# Power.net
KiCad netlist of a schematic drawn in Altium Designer
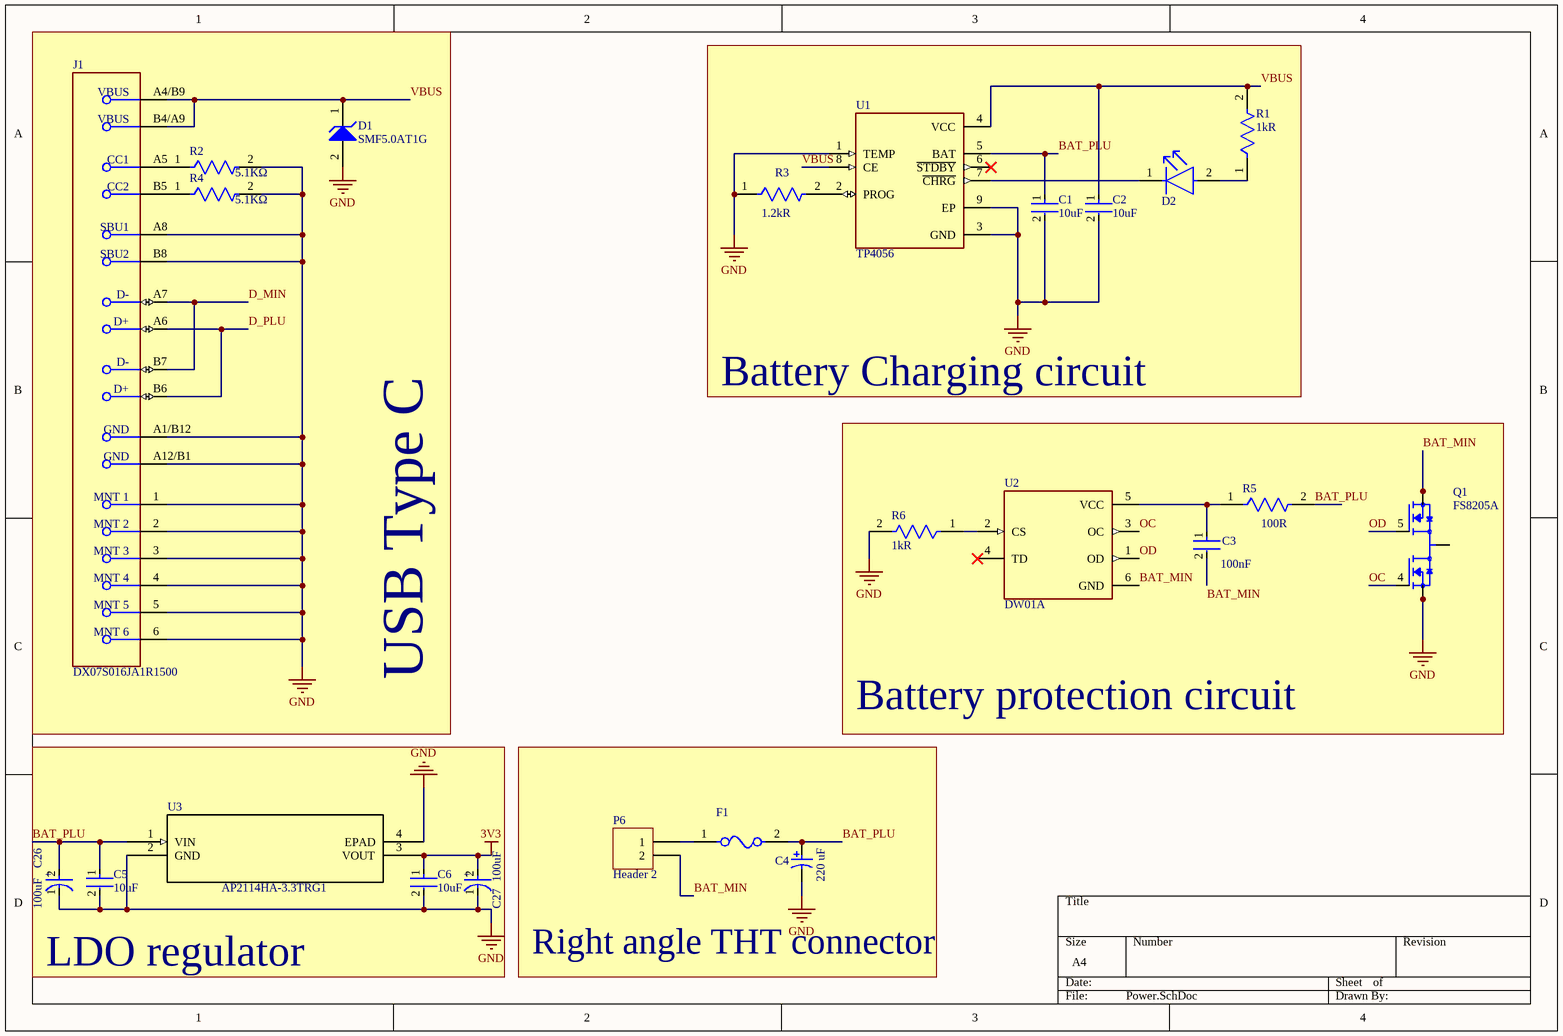
[diagram p0: Power.SchDoc]

(export (version "E")
  (design (tool "Eeschema 10.0.6"))
  (components
    (comp (ref "C1")
      (value "C0805C106J8RACAUTO")
      (footprint "FP-C0805C106J8RACAUTO-IPC_B")
      (description "CAP CER 10UF 10V X7R 0805")
      (fields
        (field (name "CAPACITANCE") "10uF")
        (field (name "TOLERANCE") "5%")
        (field (name "LCSC PART") "C15850")
      )
      (libsource (lib "Altium Content Vault") (part "02cd4be3c70576c341d710602a673aa"))
    )
    (comp (ref "C2")
      (value "C0805C106J8RACAUTO")
      (footprint "FP-C0805C106J8RACAUTO-MFG")
      (description "CAP CER 10UF 10V X7R 0805")
      (fields
        (field (name "CAPACITANCE") "10uF")
        (field (name "TOLERANCE") "5%")
        (field (name "LCSC PART") "C15850")
      )
      (libsource (lib "Altium Content Vault") (part "02cd4be3c70576c341d710602a673aa"))
    )
    (comp (ref "C3")
      (value "CC0805KKX7RYBB104")
      (footprint "FP-CC0805-EB-IPC_B")
      (description "CC0805KKX7RYBB104 Capacitor Ceramic 0.01uF 250V X7R 10% 0805 T/R")
      (fields
        (field (name "TOLERANCE") "10%")
        (field (name "CAPACITANCE") "100nF")
        (field (name "LCSC PART") "C28233")
      )
      (libsource (lib "Altium Content Vault") (part "b4654b650e69147ec39a6b967a45e02"))
    )
    (comp (ref "C4")
      (value "UUD1V221MNL1GS")
      (footprint "NIC-CAPA2-8X10_V")
      (fields
        (field (name "RATED CAPACITANCE") "220 uF")
        (field (name "MANUFACTURER") "Nichicon")
        (field (name "LCSC PART") "C2836441")
      )
      (libsource (lib "Altium Content Vault") (part "NIC-CAP-P-2"))
    )
    (comp (ref "C5")
      (value "C0805C106J8RACAUTO")
      (footprint "FP-C0805C106J8RACAUTO-IPC_B")
      (description "CAP CER 10UF 10V X7R 0805")
      (fields
        (field (name "CAPACITANCE") "10uF")
        (field (name "TOLERANCE") "5%")
        (field (name "LCSC PART") "C15850")
      )
      (libsource (lib "Altium Content Vault") (part "02cd4be3c70576c341d710602a673aa"))
    )
    (comp (ref "C6")
      (value "C0805C106J8RACAUTO")
      (footprint "FP-C0805C106J8RACAUTO-IPC_B")
      (description "CAP CER 10UF 10V X7R 0805")
      (fields
        (field (name "CAPACITANCE") "10uF")
        (field (name "TOLERANCE") "5%")
        (field (name "LCSC PART") "C15850")
      )
      (libsource (lib "Altium Content Vault") (part "02cd4be3c70576c341d710602a673aa"))
    )
    (comp (ref "C26")
      (value "10TPC100M")
      (footprint "FP-POSCAP-D2-MFG")
      (description "Molded Tantalum Polymer Capacitor 100uF 20% 10V life 2000Hours SMD 2917")
      (fields
        (field (name "CAPACITANCE") "100uF")
        (field (name "VOLTAGE") "10V")
        (field (name "TOLERANCE") "20%")
      )
      (libsource (lib "Altium Content Vault") (part "a00bbbee19879c290e62620ae7e47b1"))
    )
    (comp (ref "C27")
      (value "10TPC100M")
      (footprint "FP-POSCAP-D2-MFG")
      (description "Molded Tantalum Polymer Capacitor 100uF 20% 10V life 2000Hours SMD 2917")
      (fields
        (field (name "CAPACITANCE") "100uF")
        (field (name "VOLTAGE") "10V")
        (field (name "TOLERANCE") "20%")
      )
      (libsource (lib "Altium Content Vault") (part "a00bbbee19879c290e62620ae7e47b1"))
    )
    (comp (ref "D1")
      (value "SMF5.0AT1G")
      (footprint "ONSC-SOD-123FL-2-498_V")
      (description "200 W Transient Voltage Suppressor, 2-Pin SOD-123FL, Pb-Free, Tape and Reel")
      (fields (field (name "MANUFACTURER") "On Semiconductor") (field (name "LCSC PART") "C2857263"))
      (libsource (lib "Altium Content Vault") (part "ONSC-K1A2-2"))
    )
    (comp (ref "D2")
      (value "SML-LXT0805IW-TR")
      (footprint "FP-SML-LXT0805IW-TR-MFG")
      (description "LED RED DIFFUSED SMD")
      (fields (field (name "LCSC PART") "C2297"))
      (libsource (lib "Altium Content Vault") (part "8706943c75ba83719d021d2fdc84c58"))
    )
    (comp (ref "F1")
      (value "MF-NSMF200-2")
      (footprint "FP-MF-NSMF200-2-MFG")
      (description "PTC RESET FUSE 6V 2A 1206")
      (fields
        (field (name "MANUFACTURER") "Bourns Inc.")
        (field (name "OCTOPART") "https://octopart.com/mf-nsmf200-2-bourns-90790")
      )
      (libsource (lib "Altium Content Vault") (part "5bcf9b9f640e542cf0359d10258e979"))
    )
    (comp (ref "J1")
      (value "DX07S016JA1R1500")
      (footprint "FP-DX07S016JA1R1500-MFG")
      (description "CONN RCP USB2.0 TYP C 24P SMD RA")
      (fields (field (name "LCSC PART") "C3197885"))
      (libsource (lib "Altium Content Vault") (part "7f3e9989102a0f22bff9cb010881d34"))
    )
    (comp (ref "P6")
      (value "Header 2")
      (footprint "HDR1X2")
      (description "Header, 2-Pin")
      (fields (field (name "LCSC PART") "C32713268") (field (name "PUBLISHER") "Altium Limited"))
      (libsource (lib "Miscellaneous Connectors") (part "Header 2"))
    )
    (comp (ref "Q1")
      (value "FS8205A")
      (footprint "SOP65P640X120-8N")
      (fields (field (name "MF") "Fortune Semiconductor") (field (name "LCSC PART") "C5148694"))
      (libsource (lib "FS8205A") (part "FS8205A"))
    )
    (comp (ref "R1")
      (value "MCU0805MD1001BP100")
      (footprint "FP-MCU0805-IPC_B")
      (description "RES 1.05K OHM 0.5% 1/5W 0805")
      (fields
        (field (name "TOLERANCE") "0.1%")
        (field (name "RESISTANCE") "1kR")
        (field (name "LCSC PART") "C17513")
      )
      (libsource (lib "Altium Content Vault") (part "1029c3af85768c4190bb7ad29bc67b5"))
    )
    (comp (ref "R2")
      (value "5.1KΩ")
      (footprint "FP-AC0805-IPC_B")
      (description "RES SMD 5.1K OHM 5% 1/8W 0805")
      (fields
        (field (name "OCTOPART") "https://octopart.com/ac0805jr-075k1l-yageo-21711115")
        (field (name "MANUFACTURER") "Yageo")
      )
      (libsource (lib "Altium Content Vault") (part "1029c3af85768c4190bb7ad29bc67b5"))
    )
    (comp (ref "R3")
      (value "RMCF0805JG1K20")
      (footprint "FP-RMCF0805-IPC_B")
      (description "1.2kΩ ±5% 0.125W 0805 Thick Film Chip Resistor AEC-Q200 compliant")
      (fields
        (field (name "RESISTANCE") "1.2kR")
        (field (name "TOLERANCE") "5%")
        (field (name "LCSC PART") "C17379")
      )
      (libsource (lib "Altium Content Vault") (part "1029c3af85768c4190bb7ad29bc67b5"))
    )
    (comp (ref "R4")
      (value "5.1KΩ")
      (footprint "FP-AC0805-IPC_B")
      (description "RES SMD 5.1K OHM 5% 1/8W 0805")
      (fields
        (field (name "OCTOPART") "https://octopart.com/ac0805jr-075k1l-yageo-21711115")
        (field (name "MANUFACTURER") "Yageo")
      )
      (libsource (lib "Altium Content Vault") (part "1029c3af85768c4190bb7ad29bc67b5"))
    )
    (comp (ref "R5")
      (value "CRCW0805100RJNEAHP")
      (footprint "FP-CRCW0805-HPe3-IPC_B")
      (description "RES Thick Film, 100Ω, 5%, 0.5W, 200ppm/°C, 0805")
      (fields
        (field (name "RESISTANCE") "100R")
        (field (name "TOLERANCE") "5%")
        (field (name "LCSC PART") "C17408")
      )
      (libsource (lib "Altium Content Vault") (part "1029c3af85768c4190bb7ad29bc67b5"))
    )
    (comp (ref "R6")
      (value "MCU0805MD1001BP100")
      (footprint "FP-MCU0805-IPC_B")
      (description "RES 1.05K OHM 0.5% 1/5W 0805")
      (fields
        (field (name "TOLERANCE") "0.1%")
        (field (name "RESISTANCE") "1kR")
        (field (name "LCSC PART") "C17513")
      )
      (libsource (lib "Altium Content Vault") (part "1029c3af85768c4190bb7ad29bc67b5"))
    )
    (comp (ref "U1")
      (value "TP4056")
      (footprint "SOP127P600X175-9N")
      (description "Complete single cell Li-Ion battery with a constant current / constant voltage linear charger")
      (fields (field (name "MF") "NanJing Top Power ASIC Corp.") (field (name "LCSC PART") "C16581"))
      (libsource (lib "TP4056") (part "TP4056"))
    )
    (comp (ref "U2")
      (value "DW01A")
      (footprint "SOT95P280X145-6N")
      (description "One Cell Lithium-ion/Polymer Battery Protection IC")
      (fields (field (name "MF") "Fortune Semiconductor") (field (name "LCSC PART") "C18164398"))
      (libsource (lib "DW01A") (part "DW01A"))
    )
    (comp (ref "U3")
      (value "AP2114HA-3.3TRG1")
      (footprint "SOT-223_DIO")
      (description "Description")
      (fields
        (field (name "LCSC PART") "C460314")
        (field (name "COPYRIGHT") "Copyright (C) 2025 Ultra Librarian. All rights reserved.")
      )
      (libsource (lib "AP2114HA-3P3TRG1") (part "AP2114HA-3.3TRG1"))
    )
  )
  (nets
    (net (code "1") (name "/BAT_MIN") (class "Default")
      (node (ref "C3") (pin "2") (pinfunction "2_2") (pintype "passive"))
      (node (ref "P6") (pin "2") (pinfunction "2_2") (pintype "passive"))
      (node (ref "Q1") (pin "6") (pinfunction "S2_6") (pintype "passive"))
      (node (ref "Q1") (pin "7") (pinfunction "S2_7") (pintype "passive"))
      (node (ref "U2") (pin "6") (pinfunction "GND_6") (pintype "power_in"))
    )
    (net (code "2") (name "/BAT_PLU") (class "Default")
      (node (ref "C1") (pin "1") (pinfunction "1_1") (pintype "passive"))
      (node (ref "C26") (pin "2") (pinfunction "A_2") (pintype "passive"))
      (node (ref "C4") (pin "1") (pinfunction "1_1") (pintype "passive"))
      (node (ref "C5") (pin "1") (pinfunction "1_1") (pintype "passive"))
      (node (ref "F1") (pin "2") (pinfunction "2_2") (pintype "passive"))
      (node (ref "R5") (pin "2") (pinfunction "2_2") (pintype "passive"))
      (node (ref "U1") (pin "5") (pinfunction "BAT_5") (pintype "power_in"))
      (node (ref "U3") (pin "1") (pinfunction "VIN_1") (pintype "input"))
    )
    (net (code "3") (name "/D_MIN") (class "Default")
      (node (ref "J1") (pin "A7") (pinfunction "D-_A7") (pintype "bidirectional"))
      (node (ref "J1") (pin "B7") (pinfunction "D-_B7") (pintype "bidirectional"))
    )
    (net (code "4") (name "/D_PLU") (class "Default")
      (node (ref "J1") (pin "A6") (pinfunction "D+_A6") (pintype "bidirectional"))
      (node (ref "J1") (pin "B6") (pinfunction "D+_B6") (pintype "bidirectional"))
    )
    (net (code "5") (name "/OC") (class "Default")
      (node (ref "Q1") (pin "4") (pinfunction "G1_4") (pintype "passive"))
      (node (ref "U2") (pin "3") (pinfunction "OC_3") (pintype "output"))
    )
    (net (code "6") (name "/OD") (class "Default")
      (node (ref "Q1") (pin "5") (pinfunction "G2_5") (pintype "passive"))
      (node (ref "U2") (pin "1") (pinfunction "OD_1") (pintype "output"))
    )
    (net (code "7") (name "/VBUS") (class "Default")
      (node (ref "C2") (pin "1") (pinfunction "1_1") (pintype "passive"))
      (node (ref "D1") (pin "1") (pinfunction "K_1") (pintype "passive"))
      (node (ref "J1") (pin "A4/B9") (pinfunction "VBUS_A4/B9") (pintype "power_in"))
      (node (ref "J1") (pin "B4/A9") (pinfunction "VBUS_B4/A9") (pintype "power_in"))
      (node (ref "R1") (pin "2") (pinfunction "2_2") (pintype "passive"))
      (node (ref "U1") (pin "4") (pinfunction "VCC_4") (pintype "power_in"))
      (node (ref "U1") (pin "8") (pinfunction "CE_8") (pintype "input"))
    )
    (net (code "8") (name "3V3") (class "Default")
      (node (ref "C27") (pin "2") (pinfunction "A_2") (pintype "passive"))
      (node (ref "C6") (pin "1") (pinfunction "1_1") (pintype "passive"))
      (node (ref "U3") (pin "3") (pinfunction "VOUT_3") (pintype "power_in"))
    )
    (net (code "9") (name "GND") (class "Default")
      (node (ref "C1") (pin "2") (pinfunction "2_2") (pintype "passive"))
      (node (ref "C2") (pin "2") (pinfunction "2_2") (pintype "passive"))
      (node (ref "C26") (pin "1") (pinfunction "C_1") (pintype "passive"))
      (node (ref "C27") (pin "1") (pinfunction "C_1") (pintype "passive"))
      (node (ref "C4") (pin "2") (pinfunction "2_2") (pintype "passive"))
      (node (ref "C5") (pin "2") (pinfunction "2_2") (pintype "passive"))
      (node (ref "C6") (pin "2") (pinfunction "2_2") (pintype "passive"))
      (node (ref "D1") (pin "2") (pinfunction "A_2") (pintype "passive"))
      (node (ref "J1") (pin "1") (pinfunction "MNT_1_1") (pintype "passive"))
      (node (ref "J1") (pin "2") (pinfunction "MNT_2_2") (pintype "passive"))
      (node (ref "J1") (pin "3") (pinfunction "MNT_3_3") (pintype "passive"))
      (node (ref "J1") (pin "4") (pinfunction "MNT_4_4") (pintype "passive"))
      (node (ref "J1") (pin "5") (pinfunction "MNT_5_5") (pintype "passive"))
      (node (ref "J1") (pin "6") (pinfunction "MNT_6_6") (pintype "passive"))
      (node (ref "J1") (pin "A1/B12") (pinfunction "GND_A1/B12") (pintype "power_in"))
      (node (ref "J1") (pin "A12/B1") (pinfunction "GND_A12/B1") (pintype "power_in"))
      (node (ref "J1") (pin "A8") (pinfunction "SBU1_A8") (pintype "passive"))
      (node (ref "J1") (pin "B8") (pinfunction "SBU2_B8") (pintype "passive"))
      (node (ref "Q1") (pin "2") (pinfunction "S1_2") (pintype "passive"))
      (node (ref "Q1") (pin "3") (pinfunction "S1_3") (pintype "passive"))
      (node (ref "R2") (pin "2") (pinfunction "2_2") (pintype "passive"))
      (node (ref "R3") (pin "1") (pinfunction "1_1") (pintype "passive"))
      (node (ref "R4") (pin "2") (pinfunction "2_2") (pintype "passive"))
      (node (ref "R6") (pin "2") (pinfunction "2_2") (pintype "passive"))
      (node (ref "U1") (pin "1") (pinfunction "TEMP_1") (pintype "input"))
      (node (ref "U1") (pin "3") (pinfunction "GND_3") (pintype "power_in"))
      (node (ref "U1") (pin "9") (pinfunction "EP_9") (pintype "passive"))
      (node (ref "U3") (pin "2") (pinfunction "GND_2") (pintype "power_in"))
      (node (ref "U3") (pin "4") (pinfunction "EPAD_4") (pintype "passive"))
    )
    (net (code "10") (name "Net-(D2-A)") (class "Default")
      (node (ref "D2") (pin "2") (pinfunction "A_2") (pintype "passive"))
      (node (ref "R1") (pin "1") (pinfunction "1_1") (pintype "passive"))
    )
    (net (code "11") (name "Net-(D2-C)") (class "Default")
      (node (ref "D2") (pin "1") (pinfunction "C_1") (pintype "passive"))
      (node (ref "U1") (pin "7") (pinfunction "~{CHRG}_7") (pintype "output"))
    )
    (net (code "12") (name "Net-(F1-Pad1)") (class "Default")
      (node (ref "F1") (pin "1") (pinfunction "1_1") (pintype "passive"))
      (node (ref "P6") (pin "1") (pinfunction "1_1") (pintype "passive"))
    )
    (net (code "13") (name "Net-(J1-CC1)") (class "Default")
      (node (ref "J1") (pin "A5") (pinfunction "CC1_A5") (pintype "passive"))
      (node (ref "R2") (pin "1") (pinfunction "1_1") (pintype "passive"))
    )
    (net (code "14") (name "Net-(J1-CC2)") (class "Default")
      (node (ref "J1") (pin "B5") (pinfunction "CC2_B5") (pintype "passive"))
      (node (ref "R4") (pin "1") (pinfunction "1_1") (pintype "passive"))
    )
    (net (code "15") (name "Net-(Q1-D12-Pad1)") (class "Default")
      (node (ref "Q1") (pin "1") (pinfunction "D12_1") (pintype "passive"))
      (node (ref "Q1") (pin "8") (pinfunction "D12_8") (pintype "passive"))
    )
    (net (code "16") (name "Net-(U1-PROG)") (class "Default")
      (node (ref "R3") (pin "2") (pinfunction "2_2") (pintype "passive"))
      (node (ref "U1") (pin "2") (pinfunction "PROG_2") (pintype "bidirectional"))
    )
    (net (code "17") (name "Net-(U2-CS)") (class "Default")
      (node (ref "R6") (pin "1") (pinfunction "1_1") (pintype "passive"))
      (node (ref "U2") (pin "2") (pinfunction "CS_2") (pintype "input"))
    )
    (net (code "18") (name "Net-(U2-VCC)") (class "Default")
      (node (ref "C3") (pin "1") (pinfunction "1_1") (pintype "passive"))
      (node (ref "R5") (pin "1") (pinfunction "1_1") (pintype "passive"))
      (node (ref "U2") (pin "5") (pinfunction "VCC_5") (pintype "power_in"))
    )
    (net (code "19") (name "unconnected-(U1-~{STDBY}-Pad6)") (class "Default")
      (node (ref "U1") (pin "6") (pinfunction "~{STDBY}_6") (pintype "output+no_connect"))
    )
    (net (code "20") (name "unconnected-(U2-TD-Pad4)") (class "Default")
      (node (ref "U2") (pin "4") (pinfunction "TD_4") (pintype "passive+no_connect"))
    )
  )
)
